# YOTSUBA_GNSS-receiver_MAX_ver_1_3.net
KiCad netlist of a schematic drawn in EAGLE
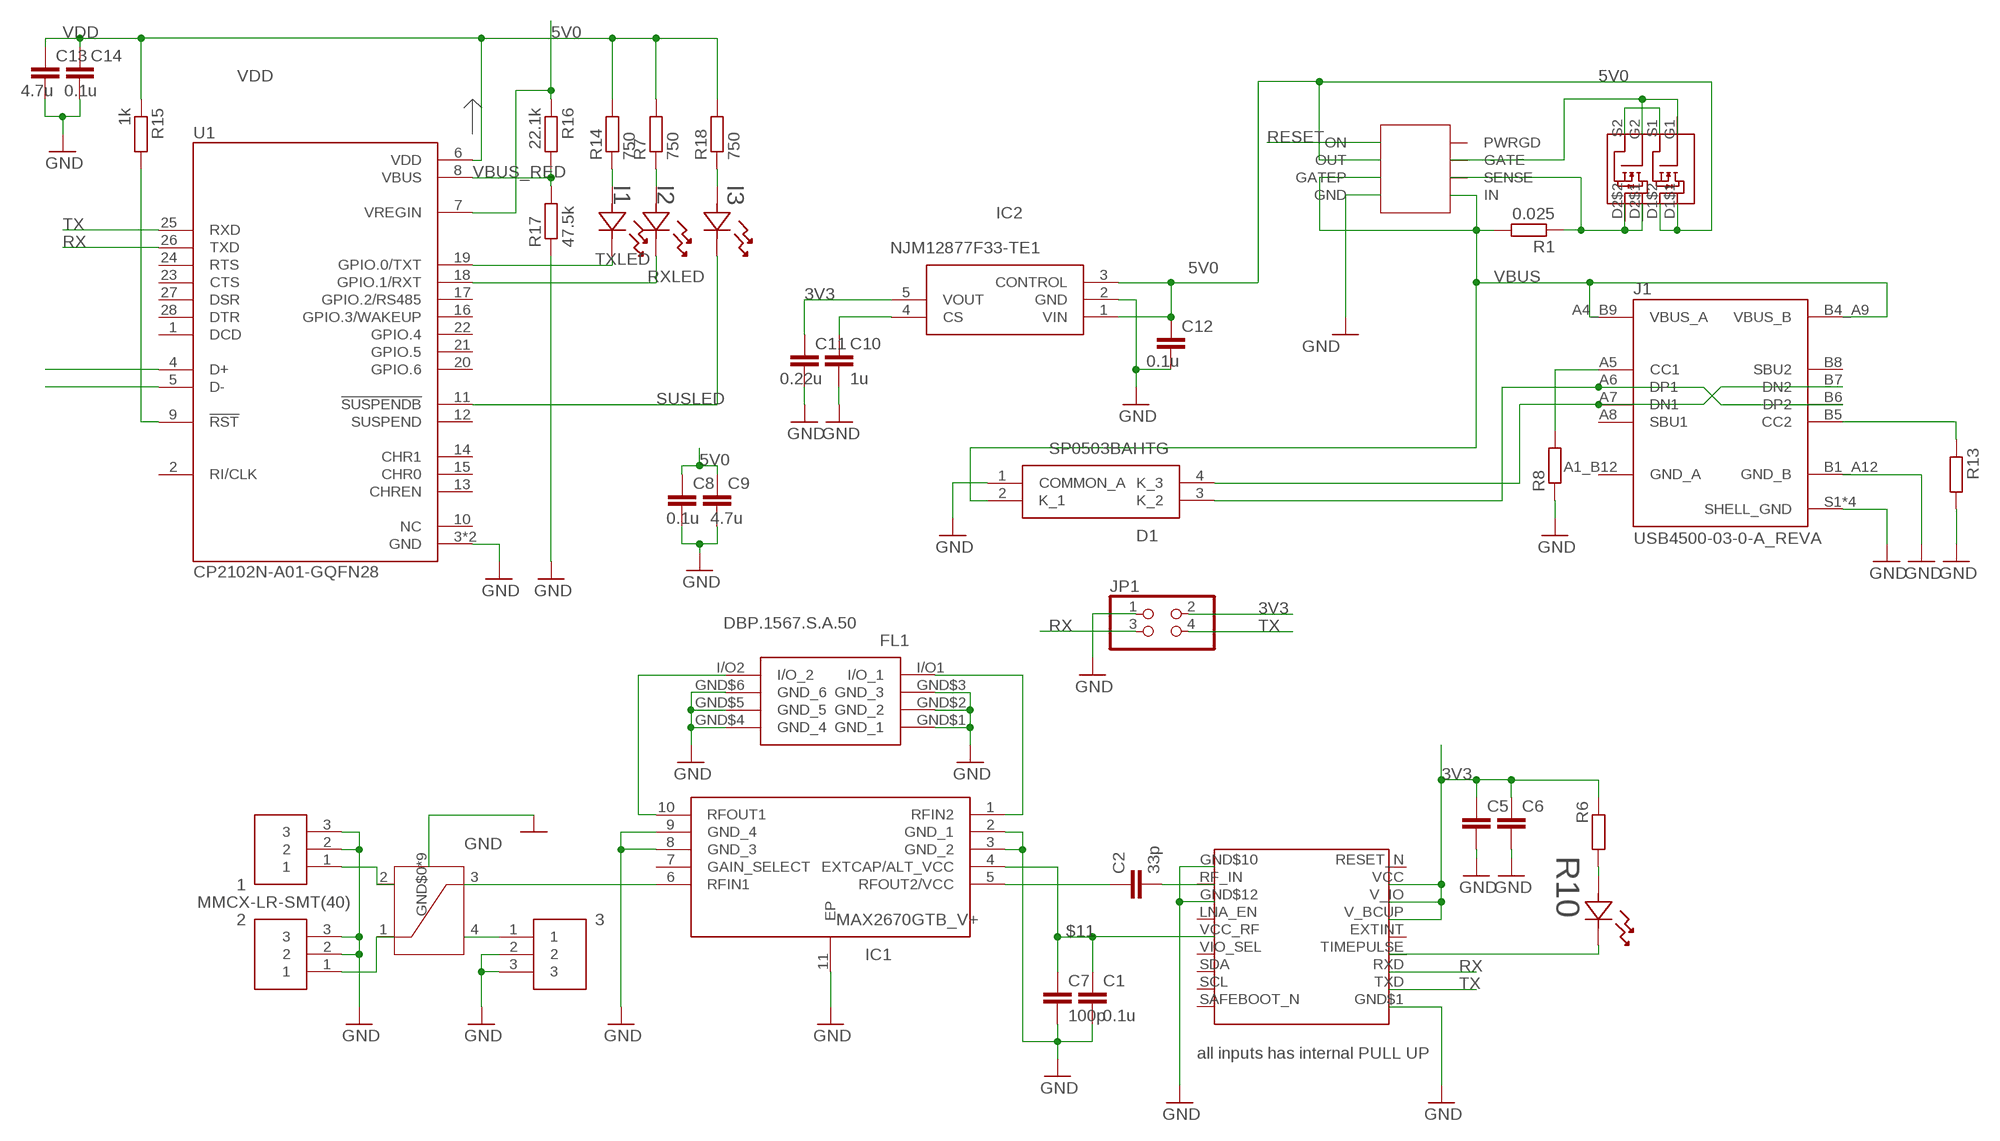
[diagram p0: schematic, sheet 1]

(export (version "E")
  (design (tool "Eeschema 10.0.6"))
  (components
    (comp (ref "1")
      (value "MMCX-LR-SMT(40)")
      (footprint "eagle-import:MMCX-LR-SMT(40)")
      (libsource (lib "eagle-import") (part "MMCX-LR-SMT(40)"))
    )
    (comp (ref "2")
      (value "MMCX-LR-SMT(40)")
      (footprint "eagle-import:MMCX-LR-SMT(40)")
      (libsource (lib "eagle-import") (part "MMCX-LR-SMT(40)"))
    )
    (comp (ref "3")
      (value "MMCX-LR-SMT(40)")
      (footprint "eagle-import:MMCX-LR-SMT(40)")
      (libsource (lib "eagle-import") (part "MMCX-LR-SMT(40)"))
    )
    (comp (ref "C1")
      (value "0.1u")
      (footprint "eagle-import:C1608")
      (libsource (lib "eagle-import") (part "C-EUC1608"))
    )
    (comp (ref "C2")
      (value "33p")
      (footprint "eagle-import:C1608")
      (libsource (lib "eagle-import") (part "C-EUC1608"))
    )
    (comp (ref "C5")
      (value "C-EUC1608")
      (footprint "eagle-import:C1608")
      (libsource (lib "eagle-import") (part "C-EUC1608"))
    )
    (comp (ref "C6")
      (value "C-EUC1608")
      (footprint "eagle-import:C1608")
      (libsource (lib "eagle-import") (part "C-EUC1608"))
    )
    (comp (ref "C7")
      (value "100p")
      (footprint "eagle-import:C1608")
      (libsource (lib "eagle-import") (part "C-EUC1608"))
    )
    (comp (ref "C8")
      (value "0.1u")
      (footprint "eagle-import:C1608")
      (libsource (lib "eagle-import") (part "C-EUC1608"))
    )
    (comp (ref "C9")
      (value "4.7u")
      (footprint "eagle-import:C1608")
      (libsource (lib "eagle-import") (part "C-EUC1608"))
    )
    (comp (ref "C10")
      (value "1u")
      (footprint "eagle-import:C1608")
      (libsource (lib "eagle-import") (part "C-EUC1608"))
    )
    (comp (ref "C11")
      (value "0.22u")
      (footprint "eagle-import:C1608")
      (libsource (lib "eagle-import") (part "C-EUC1608"))
    )
    (comp (ref "C12")
      (value "0.1u")
      (footprint "eagle-import:C1608")
      (libsource (lib "eagle-import") (part "C-EUC1608"))
    )
    (comp (ref "C13")
      (value "4.7u")
      (footprint "eagle-import:C1608")
      (libsource (lib "eagle-import") (part "C-EUC1608"))
    )
    (comp (ref "C14")
      (value "0.1u")
      (footprint "eagle-import:C1608")
      (libsource (lib "eagle-import") (part "C-EUC1608"))
    )
    (comp (ref "D1")
      (value "SP0503BAHTG")
      (footprint "eagle-import:SP0503BAHTG")
      (fields (field (name "MOUSER_PART_NUMBER") "576-SP0503BAHTG"))
      (libsource (lib "eagle-import") (part "SP0503BAHTG"))
    )
    (comp (ref "FL1")
      (value "DBP.1567.S.A.50")
      (footprint "eagle-import:DBP1567SA50")
      (libsource (lib "eagle-import") (part "DBP.1567.S.A.50"))
    )
    (comp (ref "I1")
      (value "SML-E12P8WT86")
      (footprint "eagle-import:LED_SMLD12_ROM")
      (fields (field (name "COPYRIGHT") "Copyright (C) 2023 Ultra Librarian. All rights reserved."))
      (libsource (lib "eagle-import") (part "SML-E12P8WT86"))
    )
    (comp (ref "I2")
      (value "SML-E12P8WT86")
      (footprint "eagle-import:LED_SMLD12_ROM")
      (fields (field (name "COPYRIGHT") "Copyright (C) 2023 Ultra Librarian. All rights reserved."))
      (libsource (lib "eagle-import") (part "SML-E12P8WT86"))
    )
    (comp (ref "I3")
      (value "SML-E12P8WT86")
      (footprint "eagle-import:LED_SMLD12_ROM")
      (fields (field (name "COPYRIGHT") "Copyright (C) 2023 Ultra Librarian. All rights reserved."))
      (libsource (lib "eagle-import") (part "SML-E12P8WT86"))
    )
    (comp (ref "IC1")
      (value "MAX2670GTB_V+")
      (footprint "eagle-import:SON50P300X300X80-11N")
      (fields
        (field (name "MANUFACTURER_PART_NUMBER") "MAX2670GTB/V+")
        (field (name "MOUSER_PART_NUMBER") "700-MAX2670GTB/V+")
      )
      (libsource (lib "eagle-import") (part "MAX2670GTB_V+"))
    )
    (comp (ref "IC2")
      (value "NJM12877F33-TE1")
      (footprint "eagle-import:SOT95P280X120-5N")
      (fields (field (name "MOUSER_PART_NUMBER") "513-NJM12877F33-TE1"))
      (libsource (lib "eagle-import") (part "NJM12877F33-TE1"))
    )
    (comp (ref "J1")
      (value "USB4500-03-0-A_REVA")
      (footprint "eagle-import:GCT_USB4500-03-0-A_REVA")
      (fields
        (field (name "DIGI-KEY_PART_NUMBER") "2073-USB4500-03-0-ATR-ND")
        (field (name "MF") "Global Connector Technology")
        (field (name "MP") "USB4500-03-0-A")
      )
      (libsource (lib "eagle-import") (part "USB4500-03-0-A_REVA"))
    )
    (comp (ref "JP1")
      (value "PINHD-2X2")
      (footprint "eagle-import:2X02")
      (libsource (lib "eagle-import") (part "PINHD-2X2"))
    )
    (comp (ref "R1")
      (value "0.025")
      (footprint "eagle-import:R0603")
      (libsource (lib "eagle-import") (part "R-EU_R0603"))
    )
    (comp (ref "R6")
      (value "R-EU_R0603")
      (footprint "eagle-import:R0603")
      (libsource (lib "eagle-import") (part "R-EU_R0603"))
    )
    (comp (ref "R7")
      (value "750")
      (footprint "eagle-import:R0603")
      (libsource (lib "eagle-import") (part "R-EU_R0603"))
    )
    (comp (ref "R8")
      (value "R-EU_R0603")
      (footprint "eagle-import:R0603")
      (libsource (lib "eagle-import") (part "R-EU_R0603"))
    )
    (comp (ref "R10")
      (value "SML-E12P8WT86")
      (footprint "eagle-import:LED_SMLD12_ROM")
      (fields (field (name "COPYRIGHT") "Copyright (C) 2023 Ultra Librarian. All rights reserved."))
      (libsource (lib "eagle-import") (part "SML-E12P8WT86"))
    )
    (comp (ref "R13")
      (value "R-EU_R0603")
      (footprint "eagle-import:R0603")
      (libsource (lib "eagle-import") (part "R-EU_R0603"))
    )
    (comp (ref "R14")
      (value "750")
      (footprint "eagle-import:R0603")
      (libsource (lib "eagle-import") (part "R-EU_R0603"))
    )
    (comp (ref "R15")
      (value "1k")
      (footprint "eagle-import:R0603")
      (libsource (lib "eagle-import") (part "R-EU_R0603"))
    )
    (comp (ref "R16")
      (value "22.1k")
      (footprint "eagle-import:R0603")
      (libsource (lib "eagle-import") (part "R-EU_R0603"))
    )
    (comp (ref "R17")
      (value "47.5k")
      (footprint "eagle-import:R0603")
      (libsource (lib "eagle-import") (part "R-EU_R0603"))
    )
    (comp (ref "R18")
      (value "750")
      (footprint "eagle-import:R0603")
      (libsource (lib "eagle-import") (part "R-EU_R0603"))
    )
    (comp (ref "U$1")
      (value "MAX_M10S")
      (footprint "eagle-import:MAX-M10S")
      (libsource (lib "eagle-import") (part "MAX_M10S"))
    )
    (comp (ref "U$3")
      (value "HC125.A")
      (footprint "eagle-import:HC125.A")
      (libsource (lib "eagle-import") (part "HC125.A"))
    )
    (comp (ref "U$7")
      (value "DMG6898LSD")
      (footprint "eagle-import:SOIC127P600X150-8N")
      (libsource (lib "eagle-import") (part "DMG6898LSD"))
    )
    (comp (ref "U$8")
      (value "LTC4361")
      (footprint "eagle-import:SOP65P280X100-8N")
      (libsource (lib "eagle-import") (part "LTC4361"))
    )
    (comp (ref "U1")
      (value "CP2102N-A01-GQFN28")
      (footprint "eagle-import:QFN50P500X500X80-29N")
      (fields (field (name "MF") "Silicon Labs"))
      (libsource (lib "eagle-import") (part "CP2102N-A01-GQFN28"))
    )
  )
  (nets
    (net (code "1") (name "/$11") (class "Default")
      (node (ref "C1") (pin "1") (pinfunction "1_1") (pintype "passive"))
      (node (ref "C7") (pin "1") (pinfunction "1_1") (pintype "passive"))
      (node (ref "IC1") (pin "4") (pinfunction "EXTCAP/ALT_VCC_4") (pintype "bidirectional"))
      (node (ref "U$1") (pin "VCC_RF") (pinfunction "VCC_RF_VCC_RF") (pintype "bidirectional"))
    )
    (net (code "2") (name "/3V3") (class "Default")
      (node (ref "C11") (pin "1") (pinfunction "1_1") (pintype "passive"))
      (node (ref "C5") (pin "1") (pinfunction "1_1") (pintype "passive"))
      (node (ref "C6") (pin "1") (pinfunction "1_1") (pintype "passive"))
      (node (ref "IC2") (pin "5") (pinfunction "VOUT_5") (pintype "bidirectional"))
      (node (ref "JP1") (pin "2") (pinfunction "2_2") (pintype "passive"))
      (node (ref "R6") (pin "2") (pinfunction "2_2") (pintype "passive"))
      (node (ref "U$1") (pin "VCC") (pinfunction "VCC_VCC") (pintype "bidirectional"))
      (node (ref "U$1") (pin "V_BCUP") (pinfunction "V_BCKP_V_BCUP") (pintype "bidirectional"))
      (node (ref "U$1") (pin "V_IO") (pinfunction "V_IO_V_IO") (pintype "bidirectional"))
    )
    (net (code "3") (name "/5V0") (class "Default")
      (node (ref "C12") (pin "1") (pinfunction "1_1") (pintype "passive"))
      (node (ref "C8") (pin "1") (pinfunction "1_1") (pintype "passive"))
      (node (ref "C9") (pin "1") (pinfunction "1_1") (pintype "passive"))
      (node (ref "IC2") (pin "1") (pinfunction "VIN_1") (pintype "bidirectional"))
      (node (ref "IC2") (pin "3") (pinfunction "CONTROL_3") (pintype "bidirectional"))
      (node (ref "R16") (pin "1") (pinfunction "1_1") (pintype "passive"))
      (node (ref "U$7") (pin "D1$1") (pinfunction "D1$1_D1$1") (pintype "bidirectional"))
      (node (ref "U$7") (pin "D1$2") (pinfunction "D1$2_D1$2") (pintype "bidirectional"))
      (node (ref "U$8") (pin "OUT") (pinfunction "OUT_OUT") (pintype "bidirectional"))
      (node (ref "U1") (pin "7") (pinfunction "VREGIN_7") (pintype "power_in"))
    )
    (net (code "4") (name "/D+") (class "Default")
      (node (ref "D1") (pin "3") (pinfunction "K_2_3") (pintype "bidirectional"))
      (node (ref "J1") (pin "A6") (pinfunction "DP1_A6") (pintype "bidirectional"))
      (node (ref "J1") (pin "B6") (pinfunction "DP2_B6") (pintype "bidirectional"))
      (node (ref "U1") (pin "4") (pinfunction "D+_4") (pintype "bidirectional"))
    )
    (net (code "5") (name "/D-") (class "Default")
      (node (ref "D1") (pin "4") (pinfunction "K_3_4") (pintype "bidirectional"))
      (node (ref "J1") (pin "A7") (pinfunction "DN1_A7") (pintype "bidirectional"))
      (node (ref "J1") (pin "B7") (pinfunction "DN2_B7") (pintype "bidirectional"))
      (node (ref "U1") (pin "5") (pinfunction "D-_5") (pintype "bidirectional"))
    )
    (net (code "6") (name "/GND_A") (class "Default")
      (node (ref "J1") (pin "A1_B12") (pinfunction "GND_A_A1_B12") (pintype "power_in"))
    )
    (net (code "7") (name "/RESET") (class "Default")
      (node (ref "U$8") (pin "ON") (pinfunction "ON_ON") (pintype "bidirectional"))
    )
    (net (code "8") (name "/RX") (class "Default")
      (node (ref "JP1") (pin "3") (pinfunction "3_3") (pintype "passive"))
      (node (ref "U$1") (pin "RXD") (pinfunction "RXD_RXD") (pintype "bidirectional"))
      (node (ref "U1") (pin "26") (pinfunction "TXD_26") (pintype "output"))
    )
    (net (code "9") (name "/RXLED") (class "Default")
      (node (ref "I2") (pin "1") (pinfunction "1_1") (pintype "passive"))
      (node (ref "U1") (pin "18") (pinfunction "GPIO.1/RXT_18") (pintype "bidirectional"))
    )
    (net (code "10") (name "/SUSLED") (class "Default")
      (node (ref "I3") (pin "1") (pinfunction "1_1") (pintype "passive"))
      (node (ref "U1") (pin "11") (pinfunction "~{SUSPENDB}_11") (pintype "output"))
    )
    (net (code "11") (name "/TX") (class "Default")
      (node (ref "JP1") (pin "4") (pinfunction "4_4") (pintype "passive"))
      (node (ref "U$1") (pin "TXD") (pinfunction "TXD_TXD") (pintype "bidirectional"))
      (node (ref "U1") (pin "25") (pinfunction "RXD_25") (pintype "input"))
    )
    (net (code "12") (name "/TXLED") (class "Default")
      (node (ref "I1") (pin "1") (pinfunction "1_1") (pintype "passive"))
      (node (ref "U1") (pin "19") (pinfunction "GPIO.0/TXT_19") (pintype "bidirectional"))
    )
    (net (code "13") (name "/VBUS") (class "Default")
      (node (ref "D1") (pin "2") (pinfunction "K_1_2") (pintype "bidirectional"))
      (node (ref "J1") (pin "A4_B9") (pinfunction "VBUS_A_A4_B9") (pintype "power_in"))
      (node (ref "J1") (pin "B4_A9") (pinfunction "VBUS_B_B4_A9") (pintype "power_in"))
      (node (ref "R1") (pin "2") (pinfunction "2_2") (pintype "passive"))
      (node (ref "U$8") (pin "GATEP") (pinfunction "GATEP_GATEP") (pintype "bidirectional"))
      (node (ref "U$8") (pin "IN") (pinfunction "IN_IN") (pintype "bidirectional"))
    )
    (net (code "14") (name "/VBUS_RED") (class "Default")
      (node (ref "R16") (pin "2") (pinfunction "2_2") (pintype "passive"))
      (node (ref "R17") (pin "2") (pinfunction "2_2") (pintype "passive"))
      (node (ref "U1") (pin "8") (pinfunction "VBUS_8") (pintype "power_in"))
    )
    (net (code "15") (name "/VDD") (class "Default")
      (node (ref "C13") (pin "1") (pinfunction "1_1") (pintype "passive"))
      (node (ref "C14") (pin "1") (pinfunction "1_1") (pintype "passive"))
      (node (ref "R14") (pin "2") (pinfunction "2_2") (pintype "passive"))
      (node (ref "R15") (pin "1") (pinfunction "1_1") (pintype "passive"))
      (node (ref "R18") (pin "2") (pinfunction "2_2") (pintype "passive"))
      (node (ref "R7") (pin "2") (pinfunction "2_2") (pintype "passive"))
      (node (ref "U1") (pin "6") (pinfunction "VDD_6") (pintype "power_in"))
    )
    (net (code "16") (name "GND") (class "Default")
      (node (ref "1") (pin "2") (pinfunction "2_2") (pintype "bidirectional"))
      (node (ref "1") (pin "3") (pinfunction "3_3") (pintype "bidirectional"))
      (node (ref "2") (pin "2") (pinfunction "2_2") (pintype "bidirectional"))
      (node (ref "2") (pin "3") (pinfunction "3_3") (pintype "bidirectional"))
      (node (ref "3") (pin "2") (pinfunction "2_2") (pintype "bidirectional"))
      (node (ref "3") (pin "3") (pinfunction "3_3") (pintype "bidirectional"))
      (node (ref "C1") (pin "2") (pinfunction "2_2") (pintype "passive"))
      (node (ref "C10") (pin "2") (pinfunction "2_2") (pintype "passive"))
      (node (ref "C11") (pin "2") (pinfunction "2_2") (pintype "passive"))
      (node (ref "C12") (pin "2") (pinfunction "2_2") (pintype "passive"))
      (node (ref "C13") (pin "2") (pinfunction "2_2") (pintype "passive"))
      (node (ref "C14") (pin "2") (pinfunction "2_2") (pintype "passive"))
      (node (ref "C5") (pin "2") (pinfunction "2_2") (pintype "passive"))
      (node (ref "C6") (pin "2") (pinfunction "2_2") (pintype "passive"))
      (node (ref "C7") (pin "2") (pinfunction "2_2") (pintype "passive"))
      (node (ref "C8") (pin "2") (pinfunction "2_2") (pintype "passive"))
      (node (ref "C9") (pin "2") (pinfunction "2_2") (pintype "passive"))
      (node (ref "D1") (pin "1") (pinfunction "COMMON_A_1") (pintype "bidirectional"))
      (node (ref "FL1") (pin "GND$1") (pinfunction "GND_1_GND$1") (pintype "bidirectional"))
      (node (ref "FL1") (pin "GND$2") (pinfunction "GND_2_GND$2") (pintype "bidirectional"))
      (node (ref "FL1") (pin "GND$3") (pinfunction "GND_3_GND$3") (pintype "bidirectional"))
      (node (ref "FL1") (pin "GND$4") (pinfunction "GND_4_GND$4") (pintype "bidirectional"))
      (node (ref "FL1") (pin "GND$5") (pinfunction "GND_5_GND$5") (pintype "bidirectional"))
      (node (ref "FL1") (pin "GND$6") (pinfunction "GND_6_GND$6") (pintype "bidirectional"))
      (node (ref "IC1") (pin "11") (pinfunction "EP_11") (pintype "bidirectional"))
      (node (ref "IC1") (pin "2") (pinfunction "GND_1_2") (pintype "bidirectional"))
      (node (ref "IC1") (pin "3") (pinfunction "GND_2_3") (pintype "bidirectional"))
      (node (ref "IC1") (pin "8") (pinfunction "GND_3_8") (pintype "bidirectional"))
      (node (ref "IC1") (pin "9") (pinfunction "GND_4_9") (pintype "bidirectional"))
      (node (ref "IC2") (pin "2") (pinfunction "GND_2") (pintype "bidirectional"))
      (node (ref "J1") (pin "B1_A12") (pinfunction "GND_B_B1_A12") (pintype "power_in"))
      (node (ref "J1") (pin "S1") (pinfunction "SHELL_GND_S1") (pintype "power_in"))
      (node (ref "J1") (pin "S2") (pinfunction "SHELL_GND_S2") (pintype "power_in"))
      (node (ref "J1") (pin "S3") (pinfunction "SHELL_GND_S3") (pintype "power_in"))
      (node (ref "J1") (pin "S4") (pinfunction "SHELL_GND_S4") (pintype "power_in"))
      (node (ref "JP1") (pin "1") (pinfunction "1_1") (pintype "passive"))
      (node (ref "R13") (pin "2") (pinfunction "2_2") (pintype "passive"))
      (node (ref "R17") (pin "1") (pinfunction "1_1") (pintype "passive"))
      (node (ref "R8") (pin "1") (pinfunction "1_1") (pintype "passive"))
      (node (ref "U$1") (pin "GND$1") (pinfunction "GND$1_GND$1") (pintype "bidirectional"))
      (node (ref "U$1") (pin "GND$10") (pinfunction "GND$10_GND$10") (pintype "bidirectional"))
      (node (ref "U$1") (pin "GND$12") (pinfunction "GND$12_GND$12") (pintype "bidirectional"))
      (node (ref "U$3") (pin "GND$0") (pinfunction "GND_GND$0") (pintype "bidirectional"))
      (node (ref "U$3") (pin "GND$1") (pinfunction "GND_GND$1") (pintype "bidirectional"))
      (node (ref "U$3") (pin "GND$2") (pinfunction "GND_GND$2") (pintype "bidirectional"))
      (node (ref "U$3") (pin "GND$3") (pinfunction "GND_GND$3") (pintype "bidirectional"))
      (node (ref "U$3") (pin "GND$4") (pinfunction "GND_GND$4") (pintype "bidirectional"))
      (node (ref "U$3") (pin "GND$5") (pinfunction "GND_GND$5") (pintype "bidirectional"))
      (node (ref "U$3") (pin "GND$6") (pinfunction "GND_GND$6") (pintype "bidirectional"))
      (node (ref "U$3") (pin "GND$7") (pinfunction "GND_GND$7") (pintype "bidirectional"))
      (node (ref "U$3") (pin "GND$8") (pinfunction "GND_GND$8") (pintype "bidirectional"))
      (node (ref "U$8") (pin "GND") (pinfunction "GND_GND") (pintype "bidirectional"))
      (node (ref "U1") (pin "29") (pinfunction "GND_29") (pintype "power_in"))
      (node (ref "U1") (pin "3") (pinfunction "GND_3") (pintype "power_in"))
    )
    (net (code "17") (name "Net-(1-Pad1)") (class "Default")
      (node (ref "1") (pin "1") (pinfunction "1_1") (pintype "bidirectional"))
      (node (ref "U$3") (pin "2") (pinfunction "2_2") (pintype "bidirectional"))
    )
    (net (code "18") (name "Net-(2-Pad1)") (class "Default")
      (node (ref "2") (pin "1") (pinfunction "1_1") (pintype "bidirectional"))
      (node (ref "U$3") (pin "1") (pinfunction "1_1") (pintype "bidirectional"))
    )
    (net (code "19") (name "Net-(3-Pad1)") (class "Default")
      (node (ref "3") (pin "1") (pinfunction "1_1") (pintype "bidirectional"))
      (node (ref "U$3") (pin "4") (pinfunction "4_4") (pintype "bidirectional"))
    )
    (net (code "20") (name "Net-(C2-Pad2)") (class "Default")
      (node (ref "C2") (pin "2") (pinfunction "2_2") (pintype "passive"))
      (node (ref "U$1") (pin "RF_IN") (pinfunction "RF_IN_RF_IN") (pintype "bidirectional"))
    )
    (net (code "21") (name "Net-(FL1-I{slash}O_1)") (class "Default")
      (node (ref "FL1") (pin "I/O1") (pinfunction "I/O_1_I/O1") (pintype "bidirectional"))
      (node (ref "IC1") (pin "1") (pinfunction "RFIN2_1") (pintype "bidirectional"))
    )
    (net (code "22") (name "Net-(FL1-I{slash}O_2)") (class "Default")
      (node (ref "FL1") (pin "I/O2") (pinfunction "I/O_2_I/O2") (pintype "bidirectional"))
      (node (ref "IC1") (pin "10") (pinfunction "RFOUT1_10") (pintype "bidirectional"))
    )
    (net (code "23") (name "Net-(I1-Pad2)") (class "Default")
      (node (ref "I1") (pin "2") (pinfunction "2_2") (pintype "passive"))
      (node (ref "R14") (pin "1") (pinfunction "1_1") (pintype "passive"))
    )
    (net (code "24") (name "Net-(I2-Pad2)") (class "Default")
      (node (ref "I2") (pin "2") (pinfunction "2_2") (pintype "passive"))
      (node (ref "R7") (pin "1") (pinfunction "1_1") (pintype "passive"))
    )
    (net (code "25") (name "Net-(I3-Pad2)") (class "Default")
      (node (ref "I3") (pin "2") (pinfunction "2_2") (pintype "passive"))
      (node (ref "R18") (pin "1") (pinfunction "1_1") (pintype "passive"))
    )
    (net (code "26") (name "Net-(IC1-RFIN1)") (class "Default")
      (node (ref "IC1") (pin "6") (pinfunction "RFIN1_6") (pintype "bidirectional"))
      (node (ref "U$3") (pin "3") (pinfunction "3_3") (pintype "bidirectional"))
    )
    (net (code "27") (name "Net-(IC1-RFOUT2{slash}VCC)") (class "Default")
      (node (ref "C2") (pin "1") (pinfunction "1_1") (pintype "passive"))
      (node (ref "IC1") (pin "5") (pinfunction "RFOUT2/VCC_5") (pintype "bidirectional"))
    )
    (net (code "28") (name "Net-(IC2-CS)") (class "Default")
      (node (ref "C10") (pin "1") (pinfunction "1_1") (pintype "passive"))
      (node (ref "IC2") (pin "4") (pinfunction "CS_4") (pintype "bidirectional"))
    )
    (net (code "29") (name "Net-(J1-CC1)") (class "Default")
      (node (ref "J1") (pin "A5") (pinfunction "CC1_A5") (pintype "bidirectional"))
      (node (ref "R8") (pin "2") (pinfunction "2_2") (pintype "passive"))
    )
    (net (code "30") (name "Net-(J1-CC2)") (class "Default")
      (node (ref "J1") (pin "B5") (pinfunction "CC2_B5") (pintype "bidirectional"))
      (node (ref "R13") (pin "1") (pinfunction "1_1") (pintype "passive"))
    )
    (net (code "31") (name "Net-(R1-Pad1)") (class "Default")
      (node (ref "R1") (pin "1") (pinfunction "1_1") (pintype "passive"))
      (node (ref "U$7") (pin "D2$1") (pinfunction "D2$1_D2$1") (pintype "bidirectional"))
      (node (ref "U$7") (pin "D2$2") (pinfunction "D2$2_D2$2") (pintype "bidirectional"))
      (node (ref "U$8") (pin "SENSE") (pinfunction "SENSE_SENSE") (pintype "bidirectional"))
    )
    (net (code "32") (name "Net-(R10-Pad1)") (class "Default")
      (node (ref "R10") (pin "1") (pinfunction "1_1") (pintype "passive"))
      (node (ref "U$1") (pin "TIMEPULSE") (pinfunction "TIMEPULSE_TIMEPULSE") (pintype "bidirectional"))
    )
    (net (code "33") (name "Net-(R10-Pad2)") (class "Default")
      (node (ref "R10") (pin "2") (pinfunction "2_2") (pintype "passive"))
      (node (ref "R6") (pin "1") (pinfunction "1_1") (pintype "passive"))
    )
    (net (code "34") (name "Net-(U$7-PadG1)") (class "Default")
      (node (ref "U$7") (pin "G1") (pinfunction "G1_G1") (pintype "bidirectional"))
      (node (ref "U$7") (pin "G2") (pinfunction "G2_G2") (pintype "bidirectional"))
      (node (ref "U$8") (pin "GATE") (pinfunction "GATE_GATE") (pintype "bidirectional"))
    )
    (net (code "35") (name "Net-(U$7-PadS1)") (class "Default")
      (node (ref "U$7") (pin "S1") (pinfunction "S1_S1") (pintype "bidirectional"))
      (node (ref "U$7") (pin "S2") (pinfunction "S2_S2") (pintype "bidirectional"))
    )
    (net (code "36") (name "Net-(U1-~{RST})") (class "Default")
      (node (ref "R15") (pin "2") (pinfunction "2_2") (pintype "passive"))
      (node (ref "U1") (pin "9") (pinfunction "~{RST}_9") (pintype "input"))
    )
    (net (code "37") (name "unconnected-(IC1-GAIN_SELECT-Pad7)") (class "Default")
      (node (ref "IC1") (pin "7") (pinfunction "GAIN_SELECT_7") (pintype "bidirectional"))
    )
    (net (code "38") (name "unconnected-(J1-SBU1-PadA8)") (class "Default")
      (node (ref "J1") (pin "A8") (pinfunction "SBU1_A8") (pintype "bidirectional"))
    )
    (net (code "39") (name "unconnected-(J1-SBU2-PadB8)") (class "Default")
      (node (ref "J1") (pin "B8") (pinfunction "SBU2_B8") (pintype "bidirectional"))
    )
    (net (code "40") (name "unconnected-(U$1-PadEXTINT)") (class "Default")
      (node (ref "U$1") (pin "EXTINT") (pinfunction "EXTINT_EXTINT") (pintype "bidirectional"))
    )
    (net (code "41") (name "unconnected-(U$1-PadLNA_EN)") (class "Default")
      (node (ref "U$1") (pin "LNA_EN") (pinfunction "LNA_EN_LNA_EN") (pintype "bidirectional"))
    )
    (net (code "42") (name "unconnected-(U$1-PadRESET_N)") (class "Default")
      (node (ref "U$1") (pin "RESET_N") (pinfunction "RESET_N_RESET_N") (pintype "bidirectional"))
    )
    (net (code "43") (name "unconnected-(U$1-PadSAFEBOOT_N)") (class "Default")
      (node (ref "U$1") (pin "SAFEBOOT_N") (pinfunction "SAFEBOOT_N_SAFEBOOT_N") (pintype "bidirectional"))
    )
    (net (code "44") (name "unconnected-(U$1-PadSCL)") (class "Default")
      (node (ref "U$1") (pin "SCL") (pinfunction "SCL_SCL") (pintype "bidirectional"))
    )
    (net (code "45") (name "unconnected-(U$1-PadSDA)") (class "Default")
      (node (ref "U$1") (pin "SDA") (pinfunction "SDA_SDA") (pintype "bidirectional"))
    )
    (net (code "46") (name "unconnected-(U$1-PadVIO_SEL)") (class "Default")
      (node (ref "U$1") (pin "VIO_SEL") (pinfunction "VIO_SEL_VIO_SEL") (pintype "bidirectional"))
    )
    (net (code "47") (name "unconnected-(U$8-PadPWRGD)") (class "Default")
      (node (ref "U$8") (pin "PWRGD") (pinfunction "PWRGD_PWRGD") (pintype "bidirectional"))
    )
    (net (code "48") (name "unconnected-(U1-CHR0-Pad15)") (class "Default")
      (node (ref "U1") (pin "15") (pinfunction "CHR0_15") (pintype "output"))
    )
    (net (code "49") (name "unconnected-(U1-CHR1-Pad14)") (class "Default")
      (node (ref "U1") (pin "14") (pinfunction "CHR1_14") (pintype "output"))
    )
    (net (code "50") (name "unconnected-(U1-CHREN-Pad13)") (class "Default")
      (node (ref "U1") (pin "13") (pinfunction "CHREN_13") (pintype "output"))
    )
    (net (code "51") (name "unconnected-(U1-CTS-Pad23)") (class "Default")
      (node (ref "U1") (pin "23") (pinfunction "CTS_23") (pintype "input"))
    )
    (net (code "52") (name "unconnected-(U1-DCD-Pad1)") (class "Default")
      (node (ref "U1") (pin "1") (pinfunction "DCD_1") (pintype "input"))
    )
    (net (code "53") (name "unconnected-(U1-DSR-Pad27)") (class "Default")
      (node (ref "U1") (pin "27") (pinfunction "DSR_27") (pintype "input"))
    )
    (net (code "54") (name "unconnected-(U1-DTR-Pad28)") (class "Default")
      (node (ref "U1") (pin "28") (pinfunction "DTR_28") (pintype "output"))
    )
    (net (code "55") (name "unconnected-(U1-GPIO.2{slash}RS485-Pad17)") (class "Default")
      (node (ref "U1") (pin "17") (pinfunction "GPIO.2/RS485_17") (pintype "bidirectional"))
    )
    (net (code "56") (name "unconnected-(U1-GPIO.3{slash}WAKEUP-Pad16)") (class "Default")
      (node (ref "U1") (pin "16") (pinfunction "GPIO.3/WAKEUP_16") (pintype "bidirectional"))
    )
    (net (code "57") (name "unconnected-(U1-GPIO.4-Pad22)") (class "Default")
      (node (ref "U1") (pin "22") (pinfunction "GPIO.4_22") (pintype "bidirectional"))
    )
    (net (code "58") (name "unconnected-(U1-GPIO.5-Pad21)") (class "Default")
      (node (ref "U1") (pin "21") (pinfunction "GPIO.5_21") (pintype "bidirectional"))
    )
    (net (code "59") (name "unconnected-(U1-GPIO.6-Pad20)") (class "Default")
      (node (ref "U1") (pin "20") (pinfunction "GPIO.6_20") (pintype "bidirectional"))
    )
    (net (code "60") (name "unconnected-(U1-NC-Pad10)") (class "Default")
      (node (ref "U1") (pin "10") (pinfunction "NC_10") (pintype "no_connect"))
    )
    (net (code "61") (name "unconnected-(U1-RI{slash}CLK-Pad2)") (class "Default")
      (node (ref "U1") (pin "2") (pinfunction "RI/CLK_2") (pintype "bidirectional"))
    )
    (net (code "62") (name "unconnected-(U1-RTS-Pad24)") (class "Default")
      (node (ref "U1") (pin "24") (pinfunction "RTS_24") (pintype "output"))
    )
    (net (code "63") (name "unconnected-(U1-SUSPEND-Pad12)") (class "Default")
      (node (ref "U1") (pin "12") (pinfunction "SUSPEND_12") (pintype "output"))
    )
  )
)
